# BSPD_Test_Board_manufactured_2016-12-12.net
KiCad netlist of a schematic drawn in EAGLE
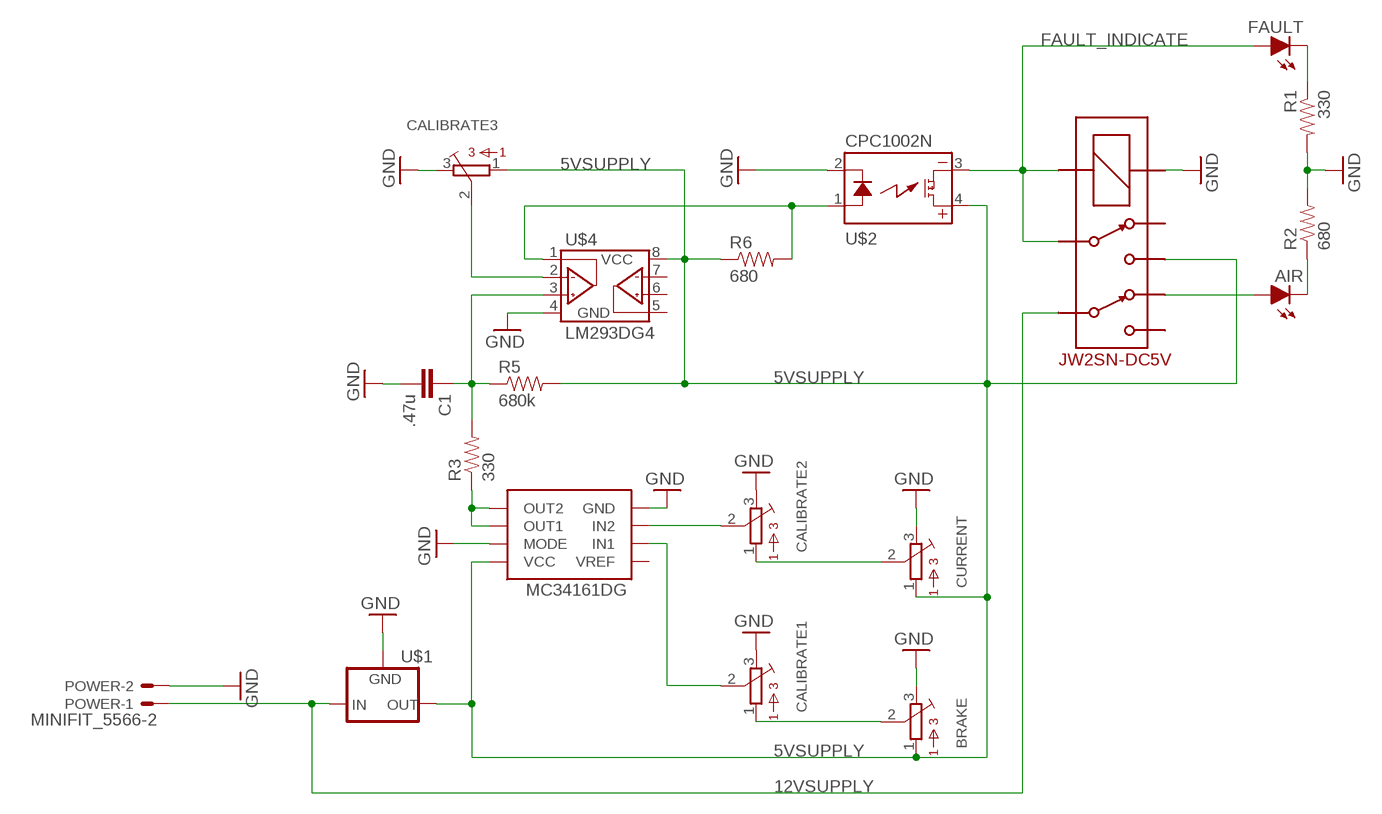
[diagram p0: schematic, sheet 1]

(export (version "E")
  (design (tool "Eeschema 10.0.6"))
  (components
    (comp (ref "AIR")
      (value "LED-5MM")
      (footprint "eagle-import:LED-5MM")
      (libsource (lib "eagle-import") (part "LED-5MM"))
    )
    (comp (ref "BRAKE")
      (value "TRIMPOT_3296C")
      (footprint "eagle-import:TRIMPOT_3296")
      (libsource (lib "eagle-import") (part "TRIMPOT_3296C"))
    )
    (comp (ref "C1")
      (value ".47u")
      (footprint "eagle-import:CAP-PTH-SMALLEZ")
      (libsource (lib "eagle-import") (part "CAPEZ"))
    )
    (comp (ref "CALIBRATE1")
      (value "TRIMPOT_3296C")
      (footprint "eagle-import:TRIMPOT_3296")
      (libsource (lib "eagle-import") (part "TRIMPOT_3296C"))
    )
    (comp (ref "CALIBRATE2")
      (value "TRIMPOT_3296C")
      (footprint "eagle-import:TRIMPOT_3296")
      (libsource (lib "eagle-import") (part "TRIMPOT_3296C"))
    )
    (comp (ref "CALIBRATE3")
      (value "TRIMPOT_3296C")
      (footprint "eagle-import:TRIMPOT_3296")
      (libsource (lib "eagle-import") (part "TRIMPOT_3296C"))
    )
    (comp (ref "CURRENT")
      (value "TRIMPOT_3296C")
      (footprint "eagle-import:TRIMPOT_3296")
      (libsource (lib "eagle-import") (part "TRIMPOT_3296C"))
    )
    (comp (ref "FAULT")
      (value "LED-5MM")
      (footprint "eagle-import:LED-5MM")
      (libsource (lib "eagle-import") (part "LED-5MM"))
    )
    (comp (ref "MC34161DG")
      (value "MC34161DG")
      (footprint "eagle-import:SOIC-08")
      (libsource (lib "eagle-import") (part "MC34161DG"))
    )
    (comp (ref "POWER")
      (value "MINIFIT_5566-2")
      (footprint "eagle-import:MINIFIT_5566-2")
      (libsource (lib "eagle-import") (part "MINIFIT_5566-2"))
    )
    (comp (ref "R1")
      (value "330")
      (footprint "eagle-import:0805")
      (libsource (lib "eagle-import") (part "RESISTOR0805-RES"))
    )
    (comp (ref "R2")
      (value "680")
      (footprint "eagle-import:0805")
      (libsource (lib "eagle-import") (part "RESISTOR0805-RES"))
    )
    (comp (ref "R3")
      (value "330")
      (footprint "eagle-import:0805")
      (libsource (lib "eagle-import") (part "RESISTOR0805-RES"))
    )
    (comp (ref "R5")
      (value "680k")
      (footprint "eagle-import:AXIAL-0.3EZ")
      (libsource (lib "eagle-import") (part "RESISTOREZ"))
    )
    (comp (ref "R6")
      (value "680")
      (footprint "eagle-import:0805")
      (libsource (lib "eagle-import") (part "RESISTOR0805-RES"))
    )
    (comp (ref "U$1")
      (value "5V_REGULATOR_LM340-NLM340MPX-5.0/NOPB")
      (footprint "eagle-import:SOT223")
      (libsource (lib "eagle-import") (part "5V_REGULATOR_LM340-NLM340MPX-5.0/NOPB"))
    )
    (comp (ref "U$2")
      (value "CPC1002N")
      (footprint "eagle-import:SOP04")
      (libsource (lib "eagle-import") (part "CPC1002N"))
    )
    (comp (ref "U$3")
      (value "DPDT_RELAY_PANASONIC_JW2SN-DC5V")
      (footprint "eagle-import:DPDT_RELAY_PANASONIC_JW2SN")
      (libsource (lib "eagle-import") (part "DPDT_RELAY_PANASONIC_JW2SN-DC5V"))
    )
    (comp (ref "U$4")
      (value "LM293DG4")
      (footprint "eagle-import:SOIC-08")
      (libsource (lib "eagle-import") (part "LM293DG4"))
    )
  )
  (nets
    (net (code "1") (name "/5VSUPPLY") (class "Default")
      (node (ref "BRAKE") (pin "1") (pinfunction "1_1") (pintype "passive"))
      (node (ref "CALIBRATE3") (pin "1") (pinfunction "1_1") (pintype "passive"))
      (node (ref "CURRENT") (pin "1") (pinfunction "1_1") (pintype "passive"))
      (node (ref "MC34161DG") (pin "8") (pinfunction "VCC_8") (pintype "passive"))
      (node (ref "R5") (pin "P$2") (pinfunction "2_P$2") (pintype "passive"))
      (node (ref "R6") (pin "1") (pinfunction "1_1") (pintype "passive"))
      (node (ref "U$1") (pin "3") (pinfunction "OUT_3") (pintype "output"))
      (node (ref "U$2") (pin "4") (pinfunction "DC+_4") (pintype "passive"))
      (node (ref "U$3") (pin "4") (pinfunction "4_4") (pintype "bidirectional"))
      (node (ref "U$4") (pin "8") (pinfunction "VCC_8") (pintype "passive"))
    )
    (net (code "2") (name "/12VSUPPLY") (class "Default")
      (node (ref "POWER") (pin "1") (pinfunction "S_1") (pintype "passive"))
      (node (ref "U$1") (pin "1") (pinfunction "IN_1") (pintype "input"))
      (node (ref "U$3") (pin "6") (pinfunction "6_6") (pintype "bidirectional"))
    )
    (net (code "3") (name "/FAULT_INDICATE") (class "Default")
      (node (ref "FAULT") (pin "A") (pinfunction "A_A") (pintype "passive"))
      (node (ref "U$2") (pin "3") (pinfunction "DC-_3") (pintype "passive"))
      (node (ref "U$3") (pin "3") (pinfunction "3_3") (pintype "bidirectional"))
      (node (ref "U$3") (pin "COIL-") (pinfunction "COIL-_COIL-") (pintype "bidirectional"))
    )
    (net (code "4") (name "GND") (class "Default")
      (node (ref "BRAKE") (pin "3") (pinfunction "3_3") (pintype "passive"))
      (node (ref "C1") (pin "2") (pinfunction "2_2") (pintype "passive"))
      (node (ref "CALIBRATE1") (pin "3") (pinfunction "3_3") (pintype "passive"))
      (node (ref "CALIBRATE2") (pin "3") (pinfunction "3_3") (pintype "passive"))
      (node (ref "CALIBRATE3") (pin "3") (pinfunction "3_3") (pintype "passive"))
      (node (ref "CURRENT") (pin "3") (pinfunction "3_3") (pintype "passive"))
      (node (ref "MC34161DG") (pin "4") (pinfunction "GND_4") (pintype "passive"))
      (node (ref "MC34161DG") (pin "7") (pinfunction "MODE_7") (pintype "passive"))
      (node (ref "POWER") (pin "2") (pinfunction "S_2") (pintype "passive"))
      (node (ref "R1") (pin "2") (pinfunction "2_2") (pintype "passive"))
      (node (ref "R2") (pin "2") (pinfunction "2_2") (pintype "passive"))
      (node (ref "U$1") (pin "2") (pinfunction "GND_2") (pintype "input"))
      (node (ref "U$1") (pin "4") (pinfunction "GND_4") (pintype "input"))
      (node (ref "U$2") (pin "2") (pinfunction "CONTROL-_2") (pintype "passive"))
      (node (ref "U$3") (pin "COIL+") (pinfunction "COIL+_COIL+") (pintype "bidirectional"))
      (node (ref "U$4") (pin "4") (pinfunction "GND_4") (pintype "passive"))
    )
    (net (code "5") (name "Net-(AIR-C)") (class "Default")
      (node (ref "AIR") (pin "K") (pinfunction "C_K") (pintype "passive"))
      (node (ref "R2") (pin "1") (pinfunction "1_1") (pintype "passive"))
    )
    (net (code "6") (name "Net-(AIR-PadA)") (class "Default")
      (node (ref "AIR") (pin "A") (pinfunction "A_A") (pintype "passive"))
      (node (ref "U$3") (pin "7") (pinfunction "7_7") (pintype "bidirectional"))
    )
    (net (code "7") (name "Net-(BRAKE-Pad2)") (class "Default")
      (node (ref "BRAKE") (pin "2") (pinfunction "2_2") (pintype "passive"))
      (node (ref "CALIBRATE1") (pin "1") (pinfunction "1_1") (pintype "passive"))
    )
    (net (code "8") (name "Net-(CALIBRATE2-Pad1)") (class "Default")
      (node (ref "CALIBRATE2") (pin "1") (pinfunction "1_1") (pintype "passive"))
      (node (ref "CURRENT") (pin "2") (pinfunction "2_2") (pintype "passive"))
    )
    (net (code "9") (name "Net-(FAULT-C)") (class "Default")
      (node (ref "FAULT") (pin "K") (pinfunction "C_K") (pintype "passive"))
      (node (ref "R1") (pin "1") (pinfunction "1_1") (pintype "passive"))
    )
    (net (code "10") (name "Net-(MC34161DG-IN1)") (class "Default")
      (node (ref "CALIBRATE1") (pin "2") (pinfunction "2_2") (pintype "passive"))
      (node (ref "MC34161DG") (pin "2") (pinfunction "IN1_2") (pintype "passive"))
    )
    (net (code "11") (name "Net-(MC34161DG-IN2)") (class "Default")
      (node (ref "CALIBRATE2") (pin "2") (pinfunction "2_2") (pintype "passive"))
      (node (ref "MC34161DG") (pin "3") (pinfunction "IN2_3") (pintype "passive"))
    )
    (net (code "12") (name "Net-(MC34161DG-OUT1)") (class "Default")
      (node (ref "MC34161DG") (pin "5") (pinfunction "OUT2_5") (pintype "passive"))
      (node (ref "MC34161DG") (pin "6") (pinfunction "OUT1_6") (pintype "passive"))
      (node (ref "R3") (pin "1") (pinfunction "1_1") (pintype "passive"))
    )
    (net (code "13") (name "Net-(R5-1)") (class "Default")
      (node (ref "C1") (pin "1") (pinfunction "1_1") (pintype "passive"))
      (node (ref "R3") (pin "2") (pinfunction "2_2") (pintype "passive"))
      (node (ref "R5") (pin "P$1") (pinfunction "1_P$1") (pintype "passive"))
      (node (ref "U$4") (pin "3") (pinfunction "1IN+_3") (pintype "passive"))
    )
    (net (code "14") (name "Net-(U$2-CONTROL+)") (class "Default")
      (node (ref "R6") (pin "2") (pinfunction "2_2") (pintype "passive"))
      (node (ref "U$2") (pin "1") (pinfunction "CONTROL+_1") (pintype "passive"))
      (node (ref "U$4") (pin "1") (pinfunction "1OUT_1") (pintype "passive"))
    )
    (net (code "15") (name "Net-(U$4-1IN-)") (class "Default")
      (node (ref "CALIBRATE3") (pin "2") (pinfunction "2_2") (pintype "passive"))
      (node (ref "U$4") (pin "2") (pinfunction "1IN-_2") (pintype "passive"))
    )
    (net (code "16") (name "unconnected-(MC34161DG-VREF-Pad1)") (class "Default")
      (node (ref "MC34161DG") (pin "1") (pinfunction "VREF_1") (pintype "passive"))
    )
    (net (code "17") (name "unconnected-(U$3-Pad2)") (class "Default")
      (node (ref "U$3") (pin "2") (pinfunction "2_2") (pintype "bidirectional"))
    )
    (net (code "18") (name "unconnected-(U$3-Pad5)") (class "Default")
      (node (ref "U$3") (pin "5") (pinfunction "5_5") (pintype "bidirectional"))
    )
    (net (code "19") (name "unconnected-(U$4-2IN+-Pad5)") (class "Default")
      (node (ref "U$4") (pin "5") (pinfunction "2IN+_5") (pintype "passive"))
    )
    (net (code "20") (name "unconnected-(U$4-2IN--Pad6)") (class "Default")
      (node (ref "U$4") (pin "6") (pinfunction "2IN-_6") (pintype "passive"))
    )
    (net (code "21") (name "unconnected-(U$4-2OUT-Pad7)") (class "Default")
      (node (ref "U$4") (pin "7") (pinfunction "2OUT_7") (pintype "passive"))
    )
  )
)
